# LED.net
KiCad netlist of a schematic drawn in Altium Designer
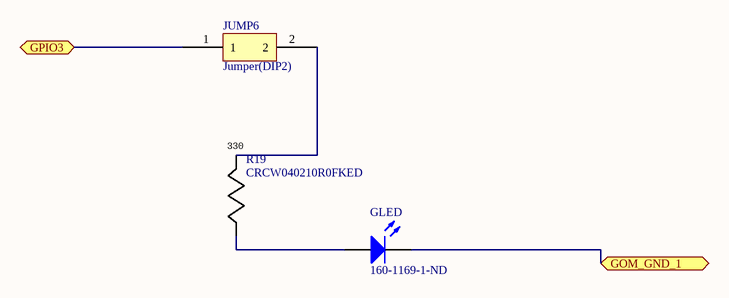
[diagram p0: LED.SchDoc]

(export (version "E")
  (design (tool "Eeschema 10.0.6"))
  (components
    (comp (ref "GLED")
      (value "160-1169-1-ND")
      (footprint "3.2X1.6X1.1")
      (description "Typical RED, GREEN, YELLOW, AMBER GaAs LED")
      (fields (field (name "PUBLISHER") "Altium Limited"))
      (libsource (lib "Miscellaneous Devices") (part "LED2"))
    )
    (comp (ref "JUMP6")
      (value "Jumper(DIP2)")
      (footprint "UmbilicalConnectors:Jumper(DIP2)")
      (libsource (lib "UmbilicalBoardV2") (part "Jumper(DIP2)"))
    )
    (comp (ref "R19")
      (value "CRCW040210R0FKED")
      (footprint "0402")
      (description "Imported")
      (fields (field (name "ALTIUM_VALUE") "330"))
      (libsource (lib "2016-03-26_18-23-46") (part "CRCW040210R0FKED"))
    )
  )
  (nets
    (net (code "1") (name "/GOM_GND_1") (class "Default")
      (node (ref "GLED") (pin "2") (pinfunction "K_2") (pintype "passive"))
    )
    (net (code "2") (name "/GPIO3") (class "Default")
      (node (ref "JUMP6") (pin "1") (pinfunction "1_1") (pintype "passive"))
    )
    (net (code "3") (name "Net-(GLED-A)") (class "Default")
      (node (ref "GLED") (pin "1") (pinfunction "A_1") (pintype "passive"))
      (node (ref "R19") (pin "2") (pinfunction "2_2") (pintype "passive"))
    )
    (net (code "4") (name "Net-(JUMP6-Pad2)") (class "Default")
      (node (ref "JUMP6") (pin "2") (pinfunction "2_2") (pintype "passive"))
      (node (ref "R19") (pin "1") (pinfunction "1_1") (pintype "passive"))
    )
  )
)
